# Output_Schematic.net
KiCad netlist of a schematic drawn in Altium Designer
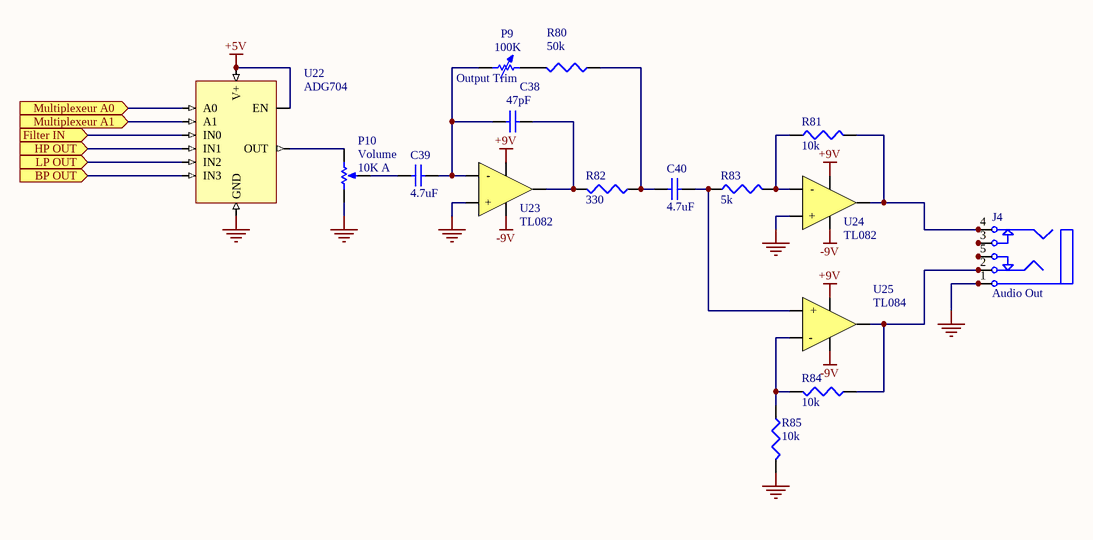
[diagram p0: Output.Schematic.SchDoc]

(export (version "E")
  (design (tool "Eeschema 10.0.6"))
  (components
    (comp (ref "C38")
      (value "47pF")
      (footprint "CAPC1608N")
      (description "Capacitor (Semiconductor SIM Model)")
      (fields (field (name "PUBLISHER") "Altium Limited"))
      (libsource (lib "Miscellaneous Devices") (part "Cap Semi"))
    )
    (comp (ref "C39")
      (value "4.7uF")
      (footprint "CAP1608N")
      (description "Capacitor (Semiconductor SIM Model)")
      (fields (field (name "PUBLISHER") "Altium Limited"))
      (libsource (lib "Miscellaneous Devices") (part "Cap Semi"))
    )
    (comp (ref "C40")
      (value "4.7uF")
      (footprint "CAPC1608N")
      (description "Capacitor (Semiconductor SIM Model)")
      (fields (field (name "PUBLISHER") "Altium Limited"))
      (libsource (lib "Miscellaneous Devices") (part "Cap Semi"))
    )
    (comp (ref "J4")
      (value "Audio Out")
      (footprint "ST-3150-5N")
      (description "3-Conductor Jack with 2 break contacts (normals) and 2 auxiliary make contacts")
      (fields (field (name "PUBLISHER") "Altium Limited"))
      (libsource (lib "Miscellaneous Connectors") (part "Phonejack Stereo SW"))
    )
    (comp (ref "P9")
      (value "Output Trim")
      (footprint "AXIAL-0.7")
      (description "Variable Resistor")
      (fields (field (name "ALTIUM_VALUE") "100K") (field (name "PUBLISHER") "Altium Limited"))
      (libsource (lib "Miscellaneous Devices") (part "Res Adj1"))
    )
    (comp (ref "P10")
      (value "Volume")
      (footprint "EC12E")
      (description "Potentiometer")
      (fields (field (name "ALTIUM_VALUE") "10K A") (field (name "PUBLISHER") "Altium Limited"))
      (libsource (lib "Miscellaneous Devices") (part "RPot"))
    )
    (comp (ref "R80")
      (value "50k")
      (footprint "CAPC1608N")
      (description "Resistor")
      (fields (field (name "PUBLISHER") "Altium Limited"))
      (libsource (lib "Miscellaneous Devices") (part "Res3"))
    )
    (comp (ref "R81")
      (value "10k")
      (footprint "CAPC1608N")
      (description "Resistor")
      (fields (field (name "PUBLISHER") "Altium Limited"))
      (libsource (lib "Miscellaneous Devices") (part "Res3"))
    )
    (comp (ref "R82")
      (value "330")
      (footprint "CAPC1608N")
      (description "Resistor")
      (fields (field (name "PUBLISHER") "Altium Limited"))
      (libsource (lib "Miscellaneous Devices") (part "Res3"))
    )
    (comp (ref "R83")
      (value "5k")
      (footprint "CAPC1608N")
      (description "Resistor")
      (fields (field (name "PUBLISHER") "Altium Limited"))
      (libsource (lib "Miscellaneous Devices") (part "Res3"))
    )
    (comp (ref "R84")
      (value "10k")
      (footprint "J1-0603")
      (description "Resistor")
      (fields (field (name "PUBLISHER") "Altium Limited"))
      (libsource (lib "Miscellaneous Devices") (part "Res3"))
    )
    (comp (ref "R85")
      (value "10k")
      (footprint "RESC6332")
      (description "Resistor")
      (fields (field (name "PUBLISHER") "Altium Limited"))
      (libsource (lib "Miscellaneous Devices") (part "Res3"))
    )
    (comp (ref "U22")
      (value "ADG704")
      (footprint "ADG704")
      (libsource (lib "SynthyTwo.Components") (part "ADG704"))
    )
    (comp (ref "U23") (value "TL082") (libsource (lib "SynthyTwo.Components") (part "TL082")))
    (comp (ref "U24") (value "TL082") (libsource (lib "SynthyTwo.Components") (part "TL082")))
    (comp (ref "U25") (value "TL084") (libsource (lib "SynthyTwo.Components") (part "TL084")))
  )
  (nets
    (net (code "1") (name "+5V") (class "Default")
      (node (ref "U22") (pin "5") (pinfunction "EN_5") (pintype "passive"))
      (node (ref "U22") (pin "6") (pinfunction "V+_6") (pintype "input"))
    )
    (net (code "2") (name "+9V") (class "Default")
      (node (ref "U23") (pin "8") (pinfunction "VCC+_8") (pintype "passive"))
      (node (ref "U24") (pin "8") (pinfunction "VCC+_8") (pintype "passive"))
      (node (ref "U25") (pin "4") (pinfunction "VCC+_4") (pintype "passive"))
    )
    (net (code "3") (name "-9V") (class "Default")
      (node (ref "U23") (pin "4") (pinfunction "VCC-_4") (pintype "passive"))
      (node (ref "U24") (pin "4") (pinfunction "VCC-_4") (pintype "passive"))
      (node (ref "U25") (pin "11") (pinfunction "VCC-_11") (pintype "passive"))
    )
    (net (code "4") (name "/BP OUT") (class "Default")
      (node (ref "U22") (pin "7") (pinfunction "IN3_7") (pintype "input"))
    )
    (net (code "5") (name "/Filter IN") (class "Default")
      (node (ref "U22") (pin "2") (pinfunction "IN0_2") (pintype "input"))
    )
    (net (code "6") (name "/HP OUT") (class "Default")
      (node (ref "U22") (pin "9") (pinfunction "IN1_9") (pintype "input"))
    )
    (net (code "7") (name "/LP OUT") (class "Default")
      (node (ref "U22") (pin "4") (pinfunction "IN2_4") (pintype "input"))
    )
    (net (code "8") (name "/Multiplexeur A0") (class "Default")
      (node (ref "U22") (pin "1") (pinfunction "A0_1") (pintype "input"))
    )
    (net (code "9") (name "/Multiplexeur A1") (class "Default")
      (node (ref "U22") (pin "10") (pinfunction "A1_10") (pintype "input"))
    )
    (net (code "10") (name "GND") (class "Default")
      (node (ref "J4") (pin "1") (pinfunction "1_1") (pintype "passive"))
      (node (ref "J4") (pin "1A") (pinfunction "1A_1A") (pintype "passive"))
      (node (ref "J4") (pin "1B") (pinfunction "1B_1B") (pintype "passive"))
      (node (ref "P10") (pin "1") (pinfunction "TOP_1") (pintype "passive"))
      (node (ref "R85") (pin "2") (pinfunction "2_2") (pintype "passive"))
      (node (ref "U22") (pin "3") (pinfunction "GND_3") (pintype "input"))
      (node (ref "U23") (pin "3") (pinfunction "+_3") (pintype "passive"))
      (node (ref "U24") (pin "3") (pinfunction "+_3") (pintype "passive"))
    )
    (net (code "11") (name "Net-(C40-Pad1)") (class "Default")
      (node (ref "C40") (pin "1") (pinfunction "1_1") (pintype "passive"))
      (node (ref "R80") (pin "1") (pinfunction "1_1") (pintype "passive"))
      (node (ref "R82") (pin "1") (pinfunction "1_1") (pintype "passive"))
    )
    (net (code "12") (name "Net-(J4-Pad3)") (class "Default")
      (node (ref "J4") (pin "3") (pinfunction "3_3") (pintype "passive"))
      (node (ref "J4") (pin "3A") (pinfunction "3A_3A") (pintype "passive"))
      (node (ref "J4") (pin "3B") (pinfunction "3B_3B") (pintype "passive"))
    )
    (net (code "13") (name "Net-(J4-Pad5)") (class "Default")
      (node (ref "J4") (pin "5") (pinfunction "5_5") (pintype "passive"))
      (node (ref "J4") (pin "5A") (pinfunction "5A_5A") (pintype "passive"))
      (node (ref "J4") (pin "5B") (pinfunction "5B_5B") (pintype "passive"))
    )
    (net (code "14") (name "Net-(P9-Pad2)") (class "Default")
      (node (ref "P9") (pin "2") (pinfunction "2_2") (pintype "passive"))
      (node (ref "R80") (pin "2") (pinfunction "2_2") (pintype "passive"))
    )
    (net (code "15") (name "Net-(P10-BOT)") (class "Default")
      (node (ref "P10") (pin "2") (pinfunction "BOT_2") (pintype "passive"))
      (node (ref "U22") (pin "8") (pinfunction "OUT_8") (pintype "output"))
    )
    (net (code "16") (name "Net-(P10-TAP)") (class "Default")
      (node (ref "C39") (pin "1") (pinfunction "1_1") (pintype "passive"))
      (node (ref "P10") (pin "3") (pinfunction "TAP_3") (pintype "passive"))
    )
    (net (code "17") (name "Net-(U23--)") (class "Default")
      (node (ref "C38") (pin "1") (pinfunction "1_1") (pintype "passive"))
      (node (ref "C39") (pin "2") (pinfunction "2_2") (pintype "passive"))
      (node (ref "P9") (pin "1") (pinfunction "1_1") (pintype "passive"))
      (node (ref "U23") (pin "2") (pinfunction "-_2") (pintype "passive"))
    )
    (net (code "18") (name "Net-(U23-OUT)") (class "Default")
      (node (ref "C38") (pin "2") (pinfunction "2_2") (pintype "passive"))
      (node (ref "R82") (pin "2") (pinfunction "2_2") (pintype "passive"))
      (node (ref "U23") (pin "1") (pinfunction "OUT_1") (pintype "passive"))
    )
    (net (code "19") (name "Net-(U24--)") (class "Default")
      (node (ref "R81") (pin "1") (pinfunction "1_1") (pintype "passive"))
      (node (ref "R83") (pin "2") (pinfunction "2_2") (pintype "passive"))
      (node (ref "U24") (pin "2") (pinfunction "-_2") (pintype "passive"))
    )
    (net (code "20") (name "Net-(U24-OUT)") (class "Default")
      (node (ref "J4") (pin "4") (pinfunction "4_4") (pintype "passive"))
      (node (ref "J4") (pin "4A") (pinfunction "4A_4A") (pintype "passive"))
      (node (ref "J4") (pin "4B") (pinfunction "4B_4B") (pintype "passive"))
      (node (ref "R81") (pin "2") (pinfunction "2_2") (pintype "passive"))
      (node (ref "U24") (pin "1") (pinfunction "OUT_1") (pintype "passive"))
    )
    (net (code "21") (name "Net-(U25-+)") (class "Default")
      (node (ref "C40") (pin "2") (pinfunction "2_2") (pintype "passive"))
      (node (ref "R83") (pin "1") (pinfunction "1_1") (pintype "passive"))
      (node (ref "U25") (pin "2") (pinfunction "+_2") (pintype "passive"))
    )
    (net (code "22") (name "Net-(U25--)") (class "Default")
      (node (ref "R84") (pin "2") (pinfunction "2_2") (pintype "passive"))
      (node (ref "R85") (pin "1") (pinfunction "1_1") (pintype "passive"))
      (node (ref "U25") (pin "3") (pinfunction "-_3") (pintype "passive"))
    )
    (net (code "23") (name "Net-(U25-OUT)") (class "Default")
      (node (ref "J4") (pin "2") (pinfunction "2_2") (pintype "passive"))
      (node (ref "J4") (pin "2A") (pinfunction "2A_2A") (pintype "passive"))
      (node (ref "J4") (pin "2B") (pinfunction "2B_2B") (pintype "passive"))
      (node (ref "R84") (pin "1") (pinfunction "1_1") (pintype "passive"))
      (node (ref "U25") (pin "1") (pinfunction "OUT_1") (pintype "passive"))
    )
  )
)
